# stm32hw03.net
KiCad netlist of a schematic drawn in EAGLE
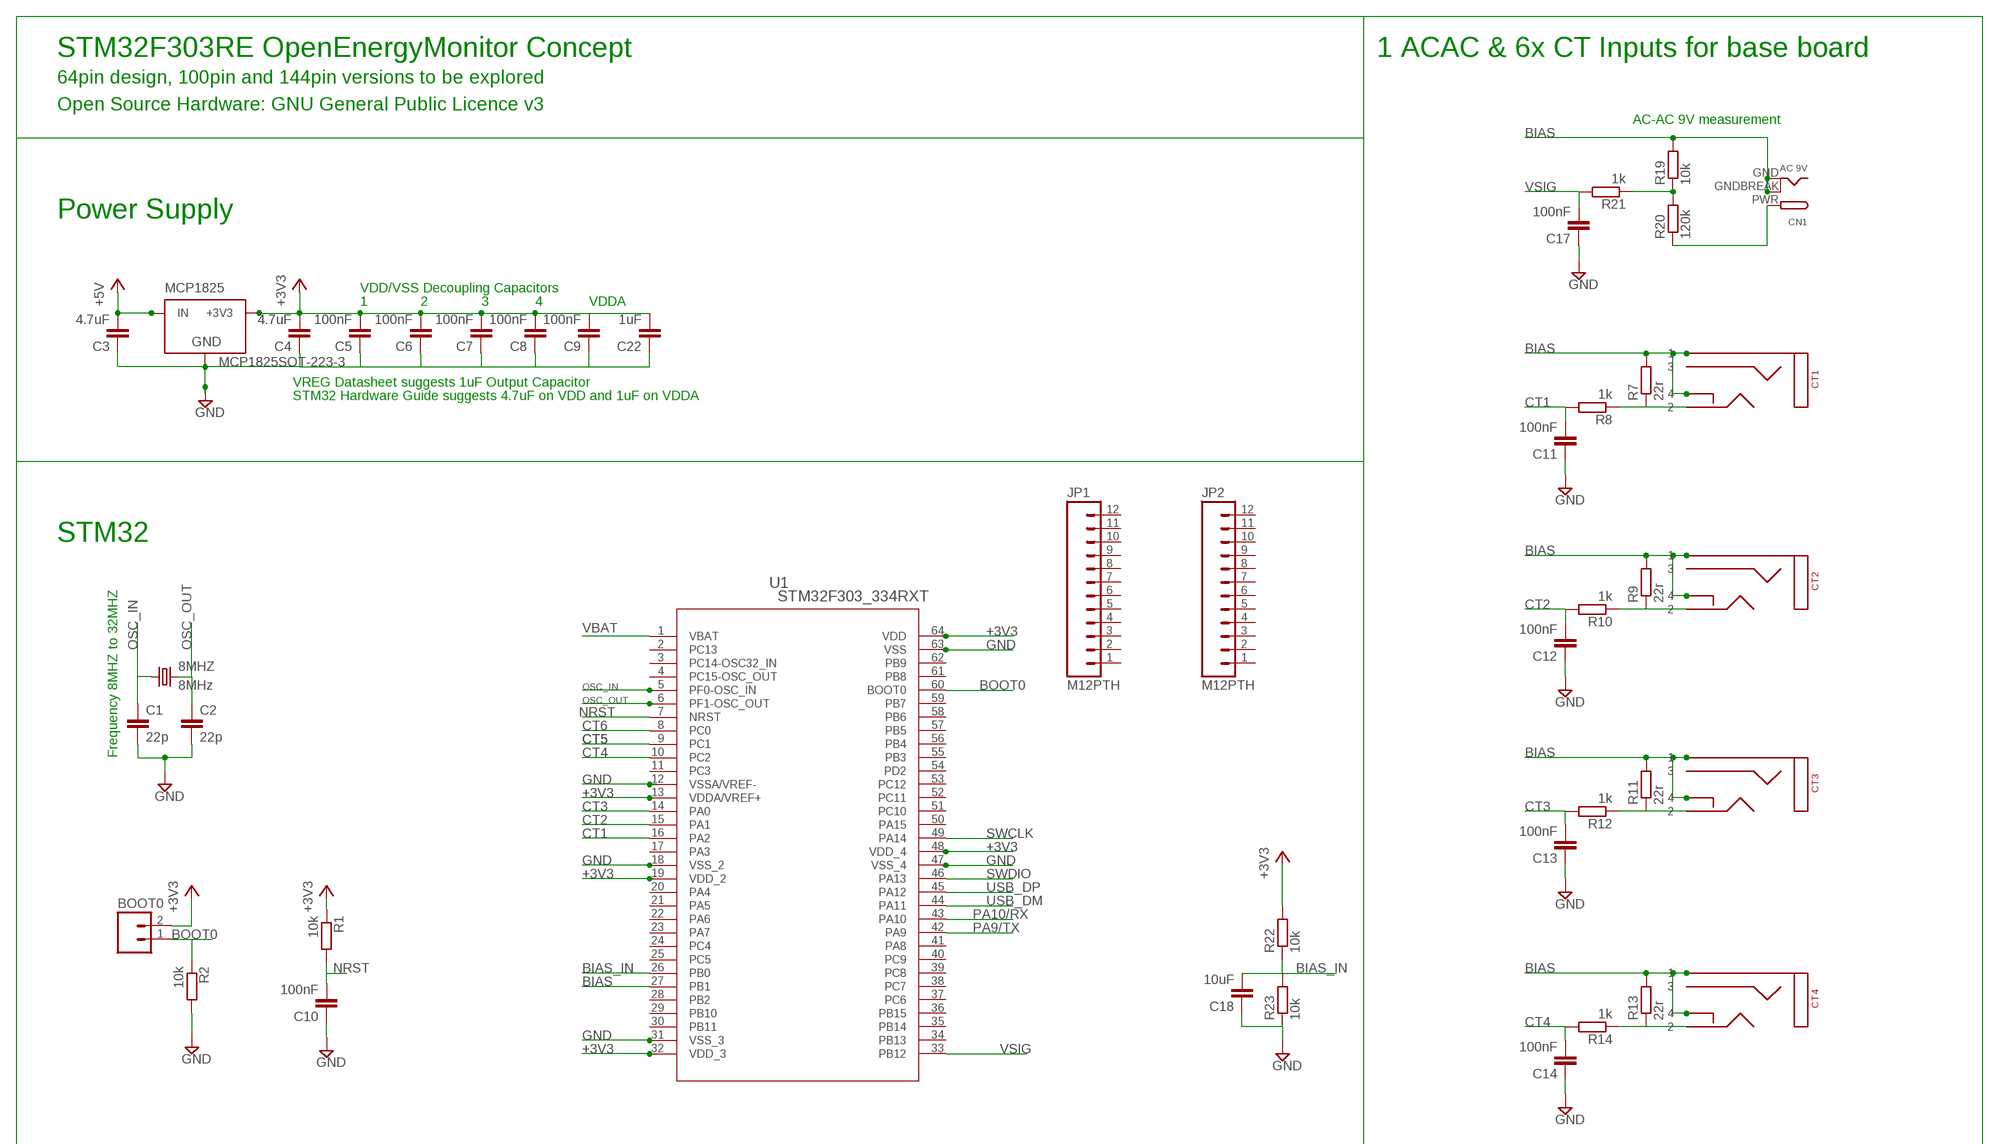
[diagram p0: schematic, sheet 1, part 1 of 2]
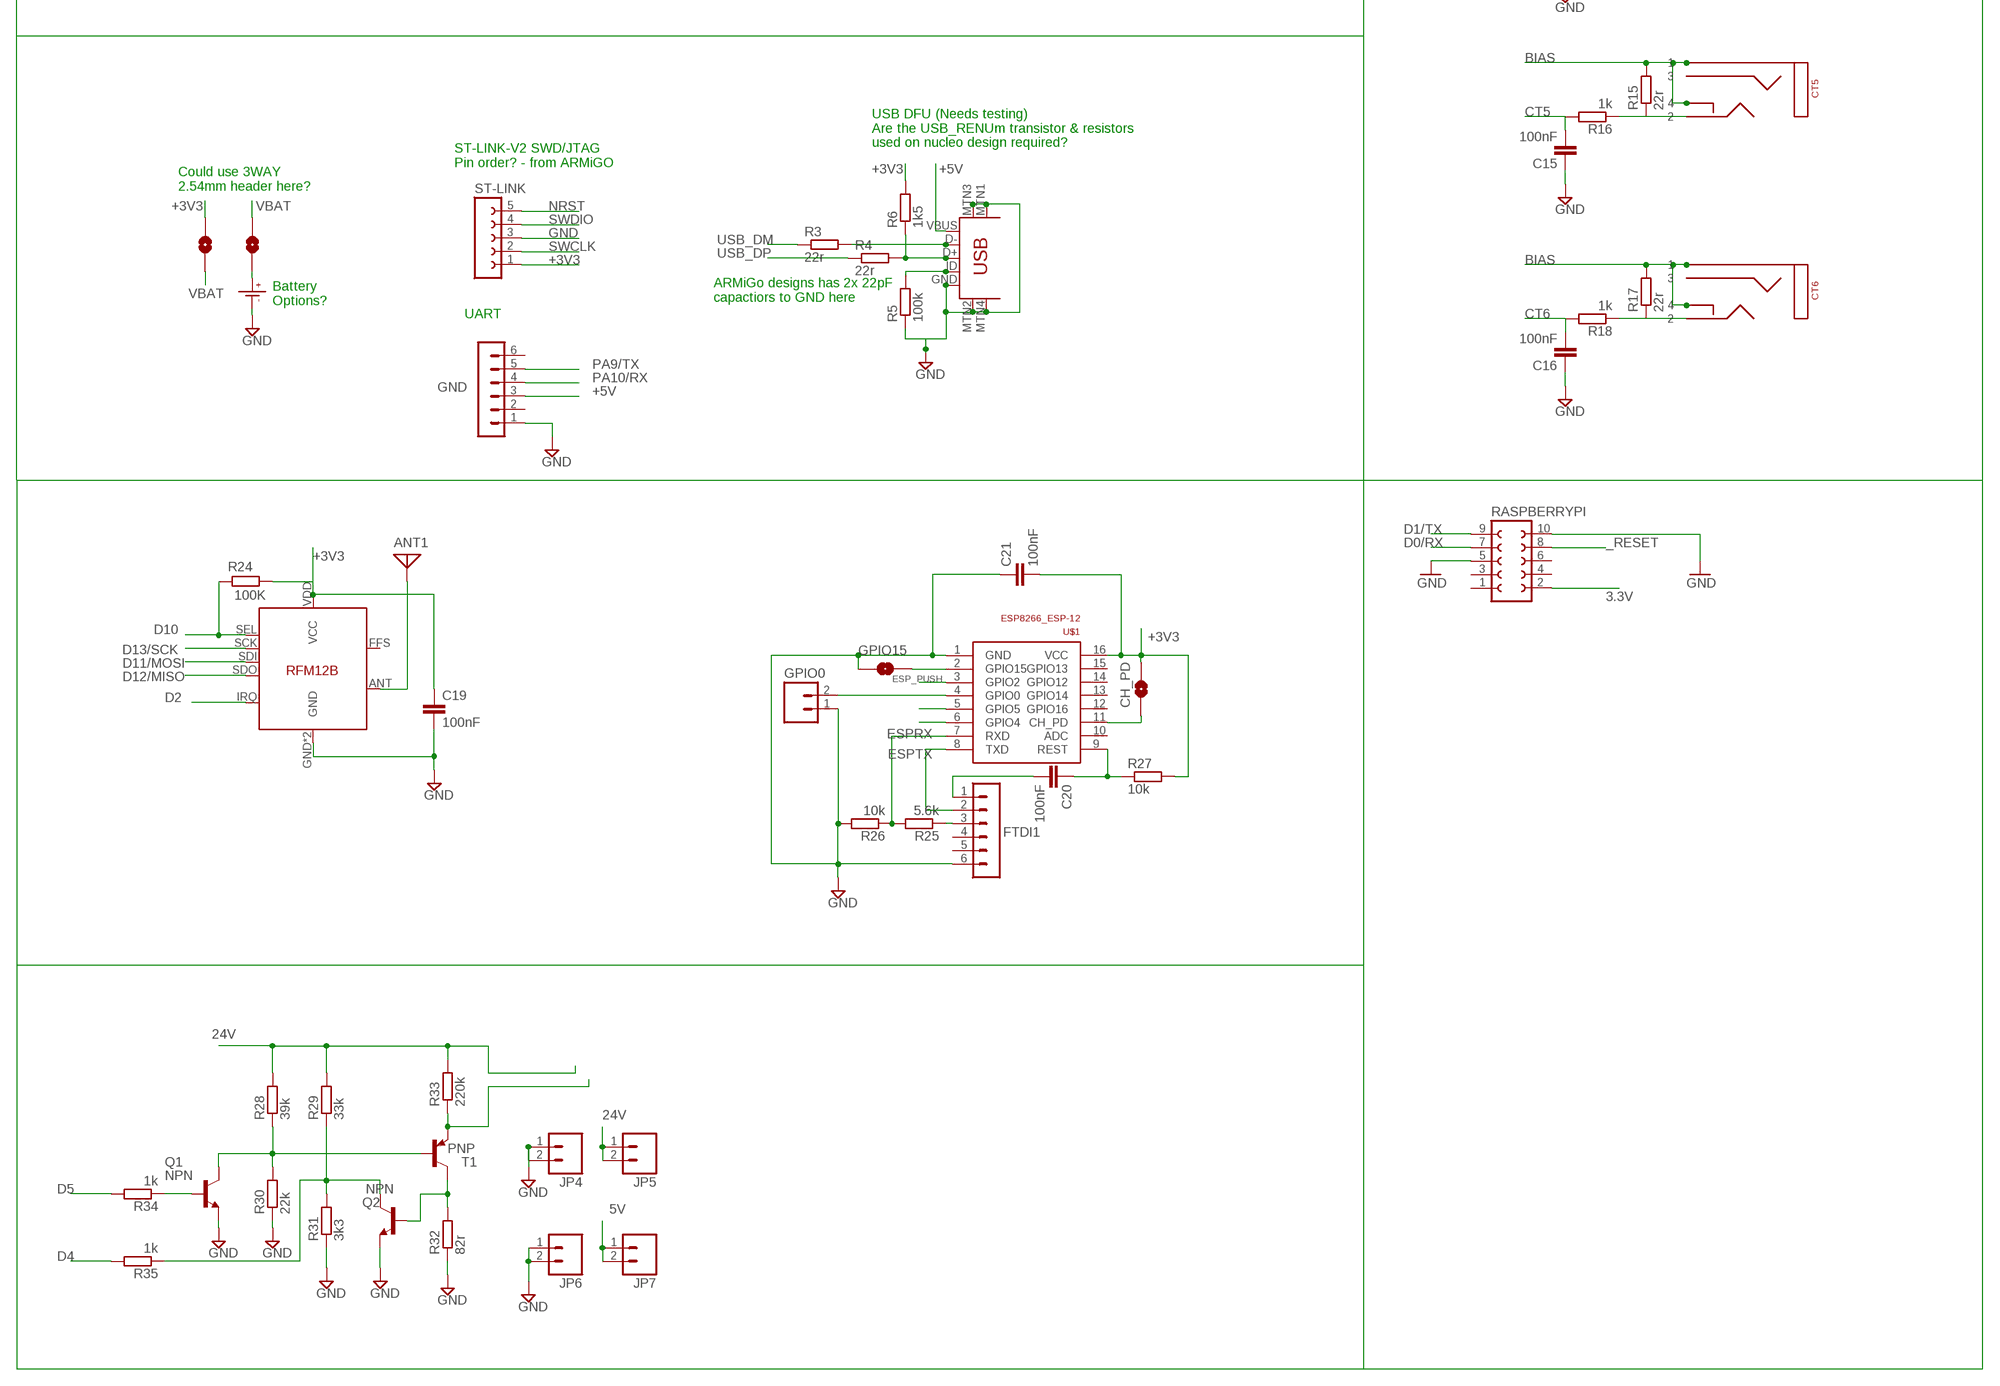
[diagram p1: schematic, sheet 1, part 2 of 2]

(export (version "E")
  (design (tool "Eeschema 10.0.6"))
  (components
    (comp (ref "3V3")
      (value "SOLDERJUMPERNO")
      (footprint "eagle-import:SJ_2S-NO")
      (libsource (lib "eagle-import") (part "SOLDERJUMPERNO"))
    )
    (comp (ref "8MHZ")
      (value "8MHz")
      (footprint "eagle-import:CRYSTAL-SMD-5X3")
      (libsource (lib "eagle-import") (part "CRYSTAL5X3"))
    )
    (comp (ref "ANT1")
      (value "ANTENNA")
      (footprint "eagle-import:PAD-01")
      (libsource (lib "eagle-import") (part "ANTENNA"))
    )
    (comp (ref "BATTERY")
      (value "SOLDERJUMPERNO")
      (footprint "eagle-import:SJ_2S-NO")
      (libsource (lib "eagle-import") (part "SOLDERJUMPERNO"))
    )
    (comp (ref "BOOT0")
      (value "M02PTH")
      (footprint "eagle-import:1X02")
      (libsource (lib "eagle-import") (part "M02PTH"))
    )
    (comp (ref "C1")
      (value "22p")
      (footprint "eagle-import:C0603")
      (libsource (lib "eagle-import") (part "C-EUC0603"))
    )
    (comp (ref "C2")
      (value "22p")
      (footprint "eagle-import:C0603")
      (libsource (lib "eagle-import") (part "C-EUC0603"))
    )
    (comp (ref "C3")
      (value "4.7uF")
      (footprint "eagle-import:C0603")
      (libsource (lib "eagle-import") (part "C-EUC0603"))
    )
    (comp (ref "C4")
      (value "4.7uF")
      (footprint "eagle-import:C0603")
      (libsource (lib "eagle-import") (part "C-EUC0603"))
    )
    (comp (ref "C5")
      (value "100nF")
      (footprint "eagle-import:C0603")
      (libsource (lib "eagle-import") (part "C-EUC0603"))
    )
    (comp (ref "C6")
      (value "100nF")
      (footprint "eagle-import:C0603")
      (libsource (lib "eagle-import") (part "C-EUC0603"))
    )
    (comp (ref "C7")
      (value "100nF")
      (footprint "eagle-import:C0603")
      (libsource (lib "eagle-import") (part "C-EUC0603"))
    )
    (comp (ref "C8")
      (value "100nF")
      (footprint "eagle-import:C0603")
      (libsource (lib "eagle-import") (part "C-EUC0603"))
    )
    (comp (ref "C9")
      (value "100nF")
      (footprint "eagle-import:C0603")
      (libsource (lib "eagle-import") (part "C-EUC0603"))
    )
    (comp (ref "C10")
      (value "100nF")
      (footprint "eagle-import:C0603")
      (libsource (lib "eagle-import") (part "C-EUC0603"))
    )
    (comp (ref "C11")
      (value "100nF")
      (footprint "eagle-import:C0603")
      (libsource (lib "eagle-import") (part "C-EUC0603"))
    )
    (comp (ref "C12")
      (value "100nF")
      (footprint "eagle-import:C0603")
      (libsource (lib "eagle-import") (part "C-EUC0603"))
    )
    (comp (ref "C13")
      (value "100nF")
      (footprint "eagle-import:C0603")
      (libsource (lib "eagle-import") (part "C-EUC0603"))
    )
    (comp (ref "C14")
      (value "100nF")
      (footprint "eagle-import:C0603")
      (libsource (lib "eagle-import") (part "C-EUC0603"))
    )
    (comp (ref "C15")
      (value "100nF")
      (footprint "eagle-import:C0603")
      (libsource (lib "eagle-import") (part "C-EUC0603"))
    )
    (comp (ref "C16")
      (value "100nF")
      (footprint "eagle-import:C0603")
      (libsource (lib "eagle-import") (part "C-EUC0603"))
    )
    (comp (ref "C17")
      (value "100nF")
      (footprint "eagle-import:C0603")
      (libsource (lib "eagle-import") (part "C-EUC0603"))
    )
    (comp (ref "C18")
      (value "10uF")
      (footprint "eagle-import:C0603")
      (libsource (lib "eagle-import") (part "C-EUC0603"))
    )
    (comp (ref "C19")
      (value "100nF")
      (footprint "eagle-import:C0603")
      (libsource (lib "eagle-import") (part "C-EUC0603"))
    )
    (comp (ref "C20")
      (value "100nF")
      (footprint "eagle-import:C0603")
      (libsource (lib "eagle-import") (part "C-EUC0603"))
    )
    (comp (ref "C21")
      (value "100nF")
      (footprint "eagle-import:C0603")
      (libsource (lib "eagle-import") (part "C-EUC0603"))
    )
    (comp (ref "C22")
      (value "1uF")
      (footprint "eagle-import:C0603")
      (libsource (lib "eagle-import") (part "C-EUC0603"))
    )
    (comp (ref "CH_PD")
      (value "SOLDERJUMPERNO")
      (footprint "eagle-import:SJ_2S-NO")
      (libsource (lib "eagle-import") (part "SOLDERJUMPERNO"))
    )
    (comp (ref "CN1")
      (value "AC 9V")
      (footprint "eagle-import:DCJACK_2MM_PTH")
      (libsource (lib "eagle-import") (part "DCBARRELPTH"))
    )
    (comp (ref "CR1220")
      (value "CR1220SMD")
      (footprint "eagle-import:CR1220SMD")
      (fields (field (name "MPN") "Harwin S8411-45R"))
      (libsource (lib "eagle-import") (part "CR1220SMD"))
    )
    (comp (ref "CT1")
      (value "STEREO_SMD")
      (footprint "eagle-import:STEREO_SMT")
      (libsource (lib "eagle-import") (part "STEREO_SMD"))
    )
    (comp (ref "CT2")
      (value "STEREO_SMD")
      (footprint "eagle-import:STEREO_SMT")
      (libsource (lib "eagle-import") (part "STEREO_SMD"))
    )
    (comp (ref "CT3")
      (value "STEREO_SMD")
      (footprint "eagle-import:STEREO_SMT")
      (libsource (lib "eagle-import") (part "STEREO_SMD"))
    )
    (comp (ref "CT4")
      (value "STEREO_SMD")
      (footprint "eagle-import:STEREO_SMT")
      (libsource (lib "eagle-import") (part "STEREO_SMD"))
    )
    (comp (ref "CT5")
      (value "STEREO_SMD")
      (footprint "eagle-import:STEREO_SMT")
      (libsource (lib "eagle-import") (part "STEREO_SMD"))
    )
    (comp (ref "CT6")
      (value "STEREO_SMD")
      (footprint "eagle-import:STEREO_SMT")
      (libsource (lib "eagle-import") (part "STEREO_SMD"))
    )
    (comp (ref "FTDI1")
      (value "FTDI")
      (footprint "eagle-import:MA06-1")
      (libsource (lib "eagle-import") (part "MA06-1"))
    )
    (comp (ref "GND")
      (value "UART")
      (footprint "eagle-import:MA06-1")
      (libsource (lib "eagle-import") (part "MA06-1"))
    )
    (comp (ref "GPIO0")
      (value "M02PTH")
      (footprint "eagle-import:1X02")
      (libsource (lib "eagle-import") (part "M02PTH"))
    )
    (comp (ref "GPIO15")
      (value "SOLDERJUMPERNO")
      (footprint "eagle-import:SJ_2S-NO")
      (libsource (lib "eagle-import") (part "SOLDERJUMPERNO"))
    )
    (comp (ref "JP1")
      (value "M12PTH")
      (footprint "eagle-import:1X12")
      (libsource (lib "eagle-import") (part "M12PTH"))
    )
    (comp (ref "JP2")
      (value "M12PTH")
      (footprint "eagle-import:1X12")
      (libsource (lib "eagle-import") (part "M12PTH"))
    )
    (comp (ref "JP4")
      (value "M02PTH")
      (footprint "eagle-import:1X02")
      (libsource (lib "eagle-import") (part "M02PTH"))
    )
    (comp (ref "JP5")
      (value "M02PTH")
      (footprint "eagle-import:1X02")
      (libsource (lib "eagle-import") (part "M02PTH"))
    )
    (comp (ref "JP6")
      (value "M02PTH")
      (footprint "eagle-import:1X02")
      (libsource (lib "eagle-import") (part "M02PTH"))
    )
    (comp (ref "JP7")
      (value "M02PTH")
      (footprint "eagle-import:1X02")
      (libsource (lib "eagle-import") (part "M02PTH"))
    )
    (comp (ref "MCP1825")
      (value "MCP1825SOT-223-3")
      (footprint "eagle-import:SOT-223")
      (libsource (lib "eagle-import") (part "MCP1825SOT-223-3"))
    )
    (comp (ref "Q1")
      (value "NPN")
      (footprint "eagle-import:SOT23-BEC")
      (libsource (lib "eagle-import") (part "BC849SMD"))
    )
    (comp (ref "Q2")
      (value "NPN")
      (footprint "eagle-import:SOT23-BEC")
      (libsource (lib "eagle-import") (part "BC849SMD"))
    )
    (comp (ref "R1")
      (value "10k")
      (footprint "eagle-import:R0603")
      (libsource (lib "eagle-import") (part "R-EU_R0603"))
    )
    (comp (ref "R2")
      (value "10k")
      (footprint "eagle-import:R0603")
      (libsource (lib "eagle-import") (part "R-EU_R0603"))
    )
    (comp (ref "R3")
      (value "22r")
      (footprint "eagle-import:R0603")
      (libsource (lib "eagle-import") (part "R-EU_R0603"))
    )
    (comp (ref "R4")
      (value "22r")
      (footprint "eagle-import:R0603")
      (libsource (lib "eagle-import") (part "R-EU_R0603"))
    )
    (comp (ref "R5")
      (value "100k")
      (footprint "eagle-import:R0603")
      (libsource (lib "eagle-import") (part "R-EU_R0603"))
    )
    (comp (ref "R6")
      (value "1k5")
      (footprint "eagle-import:R0603")
      (libsource (lib "eagle-import") (part "R-EU_R0603"))
    )
    (comp (ref "R7")
      (value "22r")
      (footprint "eagle-import:R0603")
      (libsource (lib "eagle-import") (part "R-EU_R0603"))
    )
    (comp (ref "R8")
      (value "1k")
      (footprint "eagle-import:R0603")
      (libsource (lib "eagle-import") (part "R-EU_R0603"))
    )
    (comp (ref "R9")
      (value "22r")
      (footprint "eagle-import:R0603")
      (libsource (lib "eagle-import") (part "R-EU_R0603"))
    )
    (comp (ref "R10")
      (value "1k")
      (footprint "eagle-import:R0603")
      (libsource (lib "eagle-import") (part "R-EU_R0603"))
    )
    (comp (ref "R11")
      (value "22r")
      (footprint "eagle-import:R0603")
      (libsource (lib "eagle-import") (part "R-EU_R0603"))
    )
    (comp (ref "R12")
      (value "1k")
      (footprint "eagle-import:R0603")
      (libsource (lib "eagle-import") (part "R-EU_R0603"))
    )
    (comp (ref "R13")
      (value "22r")
      (footprint "eagle-import:R0603")
      (libsource (lib "eagle-import") (part "R-EU_R0603"))
    )
    (comp (ref "R14")
      (value "1k")
      (footprint "eagle-import:R0603")
      (libsource (lib "eagle-import") (part "R-EU_R0603"))
    )
    (comp (ref "R15")
      (value "22r")
      (footprint "eagle-import:R0603")
      (libsource (lib "eagle-import") (part "R-EU_R0603"))
    )
    (comp (ref "R16")
      (value "1k")
      (footprint "eagle-import:R0603")
      (libsource (lib "eagle-import") (part "R-EU_R0603"))
    )
    (comp (ref "R17")
      (value "22r")
      (footprint "eagle-import:R0603")
      (libsource (lib "eagle-import") (part "R-EU_R0603"))
    )
    (comp (ref "R18")
      (value "1k")
      (footprint "eagle-import:R0603")
      (libsource (lib "eagle-import") (part "R-EU_R0603"))
    )
    (comp (ref "R19")
      (value "10k")
      (footprint "eagle-import:R0603")
      (libsource (lib "eagle-import") (part "R-EU_R0603"))
    )
    (comp (ref "R20")
      (value "120k")
      (footprint "eagle-import:R0603")
      (libsource (lib "eagle-import") (part "R-EU_R0603"))
    )
    (comp (ref "R21")
      (value "1k")
      (footprint "eagle-import:R0603")
      (libsource (lib "eagle-import") (part "R-EU_R0603"))
    )
    (comp (ref "R22")
      (value "10k")
      (footprint "eagle-import:R0603")
      (libsource (lib "eagle-import") (part "R-EU_R0603"))
    )
    (comp (ref "R23")
      (value "10k")
      (footprint "eagle-import:R0603")
      (libsource (lib "eagle-import") (part "R-EU_R0603"))
    )
    (comp (ref "R24")
      (value "100K")
      (footprint "eagle-import:R0603")
      (libsource (lib "eagle-import") (part "R-EU_R0603"))
    )
    (comp (ref "R25")
      (value "5.6k")
      (footprint "eagle-import:R0603")
      (libsource (lib "eagle-import") (part "R-EU_R0603"))
    )
    (comp (ref "R26")
      (value "10k")
      (footprint "eagle-import:R0603")
      (libsource (lib "eagle-import") (part "R-EU_R0603"))
    )
    (comp (ref "R27")
      (value "10k")
      (footprint "eagle-import:R0603")
      (libsource (lib "eagle-import") (part "R-EU_R0603"))
    )
    (comp (ref "R28")
      (value "39k")
      (footprint "eagle-import:R0603")
      (libsource (lib "eagle-import") (part "R-EU_R0603"))
    )
    (comp (ref "R29")
      (value "33k")
      (footprint "eagle-import:R0603")
      (libsource (lib "eagle-import") (part "R-EU_R0603"))
    )
    (comp (ref "R30")
      (value "22k")
      (footprint "eagle-import:R0603")
      (libsource (lib "eagle-import") (part "R-EU_R0603"))
    )
    (comp (ref "R31")
      (value "3k3")
      (footprint "eagle-import:R0603")
      (libsource (lib "eagle-import") (part "R-EU_R0603"))
    )
    (comp (ref "R32")
      (value "82r")
      (footprint "eagle-import:R0603")
      (libsource (lib "eagle-import") (part "R-EU_R0603"))
    )
    (comp (ref "R33")
      (value "220k")
      (footprint "eagle-import:R0603")
      (libsource (lib "eagle-import") (part "R-EU_R0603"))
    )
    (comp (ref "R34")
      (value "1k")
      (footprint "eagle-import:R0603")
      (libsource (lib "eagle-import") (part "R-EU_R0603"))
    )
    (comp (ref "R35")
      (value "1k")
      (footprint "eagle-import:R0603")
      (libsource (lib "eagle-import") (part "R-EU_R0603"))
    )
    (comp (ref "RASPBERRYPI")
      (value "FE05-2")
      (footprint "eagle-import:FE05-2")
      (libsource (lib "eagle-import") (part "FE05-2"))
    )
    (comp (ref "ST-LINK")
      (value "FE05-1")
      (footprint "eagle-import:FE05-1")
      (libsource (lib "eagle-import") (part "FE05-1"))
    )
    (comp (ref "T1")
      (value "PNP")
      (footprint "eagle-import:SOT23")
      (libsource (lib "eagle-import") (part "BCX71SMD"))
    )
    (comp (ref "U$1")
      (value "ESP8266_ESP-12")
      (footprint "eagle-import:ESP8266-ESP12")
      (libsource (lib "eagle-import") (part "ESP8266_ESP-12"))
    )
    (comp (ref "U$10")
      (value "USB-MINIB-5PIN")
      (footprint "eagle-import:USB-MINIB-CISECO")
      (libsource (lib "eagle-import") (part "USB-MINIB-5PIN"))
    )
    (comp (ref "U$14")
      (value "RFM12B")
      (footprint "eagle-import:RFM12B")
      (libsource (lib "eagle-import") (part "RFM12B"))
    )
    (comp (ref "U1")
      (value "STM32F303_334RXT")
      (footprint "eagle-import:LQFP64-10X10MM")
      (fields (field (name "MANUFACTURER_PART_NUMBER") "stm32f303_334rxt"))
      (libsource (lib "eagle-import") (part "STM32F303_334RXT"))
    )
  )
  (nets
    (net (code "1") (name "+3V3") (class "Default")
      (node (ref "3V3") (pin "1") (pinfunction "1_1") (pintype "passive"))
      (node (ref "BOOT0") (pin "2") (pinfunction "2_2") (pintype "passive"))
      (node (ref "C19") (pin "1") (pinfunction "1_1") (pintype "passive"))
      (node (ref "C21") (pin "2") (pinfunction "2_2") (pintype "passive"))
      (node (ref "C22") (pin "2") (pinfunction "2_2") (pintype "passive"))
      (node (ref "C4") (pin "2") (pinfunction "2_2") (pintype "passive"))
      (node (ref "C5") (pin "2") (pinfunction "2_2") (pintype "passive"))
      (node (ref "C6") (pin "2") (pinfunction "2_2") (pintype "passive"))
      (node (ref "C7") (pin "2") (pinfunction "2_2") (pintype "passive"))
      (node (ref "C8") (pin "2") (pinfunction "2_2") (pintype "passive"))
      (node (ref "C9") (pin "2") (pinfunction "2_2") (pintype "passive"))
      (node (ref "CH_PD") (pin "1") (pinfunction "1_1") (pintype "passive"))
      (node (ref "MCP1825") (pin "3") (pinfunction "+3V3_3") (pintype "power_in"))
      (node (ref "R1") (pin "1") (pinfunction "1_1") (pintype "passive"))
      (node (ref "R22") (pin "2") (pinfunction "2_2") (pintype "passive"))
      (node (ref "R24") (pin "1") (pinfunction "1_1") (pintype "passive"))
      (node (ref "R27") (pin "2") (pinfunction "2_2") (pintype "passive"))
      (node (ref "R6") (pin "2") (pinfunction "2_2") (pintype "passive"))
      (node (ref "ST-LINK") (pin "1") (pinfunction "1_1") (pintype "passive"))
      (node (ref "U$1") (pin "16") (pinfunction "VCC_16") (pintype "bidirectional"))
      (node (ref "U$14") (pin "VDD") (pinfunction "VCC_VDD") (pintype "power_in"))
      (node (ref "U1") (pin "13") (pinfunction "VDDA/VREF+_13") (pintype "power_in"))
      (node (ref "U1") (pin "19") (pinfunction "VDD_2_19") (pintype "power_in"))
      (node (ref "U1") (pin "32") (pinfunction "VDD_3_32") (pintype "power_in"))
      (node (ref "U1") (pin "48") (pinfunction "VDD_4_48") (pintype "power_in"))
      (node (ref "U1") (pin "64") (pinfunction "VDD_64") (pintype "power_in"))
    )
    (net (code "2") (name "+5V") (class "Default")
      (node (ref "C3") (pin "2") (pinfunction "2_2") (pintype "passive"))
      (node (ref "GND") (pin "3") (pinfunction "3_3") (pintype "passive"))
      (node (ref "MCP1825") (pin "1") (pinfunction "IN_1") (pintype "power_in"))
      (node (ref "U$10") (pin "VBUS") (pinfunction "VBUS_VBUS") (pintype "bidirectional"))
    )
    (net (code "3") (name "/3.3V") (class "Default")
      (node (ref "RASPBERRYPI") (pin "2") (pinfunction "2_2") (pintype "passive"))
    )
    (net (code "4") (name "/5V") (class "Default")
      (node (ref "JP7") (pin "1") (pinfunction "1_1") (pintype "passive"))
      (node (ref "JP7") (pin "2") (pinfunction "2_2") (pintype "passive"))
    )
    (net (code "5") (name "/24V") (class "Default")
      (node (ref "JP5") (pin "1") (pinfunction "1_1") (pintype "passive"))
      (node (ref "JP5") (pin "2") (pinfunction "2_2") (pintype "passive"))
      (node (ref "R28") (pin "2") (pinfunction "2_2") (pintype "passive"))
      (node (ref "R29") (pin "2") (pinfunction "2_2") (pintype "passive"))
      (node (ref "R33") (pin "2") (pinfunction "2_2") (pintype "passive"))
    )
    (net (code "6") (name "/BIAS") (class "Default")
      (node (ref "CN1") (pin "GND") (pinfunction "GND_GND") (pintype "power_in"))
      (node (ref "CN1") (pin "GNDBREAK") (pinfunction "GNDBREAK_GNDBREAK") (pintype "power_in"))
      (node (ref "CT1") (pin "P$1") (pinfunction "1_P$1") (pintype "bidirectional"))
      (node (ref "CT1") (pin "P$4") (pinfunction "4_P$4") (pintype "bidirectional"))
      (node (ref "CT2") (pin "P$1") (pinfunction "1_P$1") (pintype "bidirectional"))
      (node (ref "CT2") (pin "P$4") (pinfunction "4_P$4") (pintype "bidirectional"))
      (node (ref "CT3") (pin "P$1") (pinfunction "1_P$1") (pintype "bidirectional"))
      (node (ref "CT3") (pin "P$4") (pinfunction "4_P$4") (pintype "bidirectional"))
      (node (ref "CT4") (pin "P$1") (pinfunction "1_P$1") (pintype "bidirectional"))
      (node (ref "CT4") (pin "P$4") (pinfunction "4_P$4") (pintype "bidirectional"))
      (node (ref "CT5") (pin "P$1") (pinfunction "1_P$1") (pintype "bidirectional"))
      (node (ref "CT5") (pin "P$4") (pinfunction "4_P$4") (pintype "bidirectional"))
      (node (ref "CT6") (pin "P$1") (pinfunction "1_P$1") (pintype "bidirectional"))
      (node (ref "CT6") (pin "P$4") (pinfunction "4_P$4") (pintype "bidirectional"))
      (node (ref "R11") (pin "2") (pinfunction "2_2") (pintype "passive"))
      (node (ref "R13") (pin "2") (pinfunction "2_2") (pintype "passive"))
      (node (ref "R15") (pin "2") (pinfunction "2_2") (pintype "passive"))
      (node (ref "R17") (pin "2") (pinfunction "2_2") (pintype "passive"))
      (node (ref "R19") (pin "2") (pinfunction "2_2") (pintype "passive"))
      (node (ref "R7") (pin "2") (pinfunction "2_2") (pintype "passive"))
      (node (ref "R9") (pin "2") (pinfunction "2_2") (pintype "passive"))
      (node (ref "U1") (pin "27") (pinfunction "PB1_27") (pintype "bidirectional"))
    )
    (net (code "7") (name "/BIAS_IN") (class "Default")
      (node (ref "C18") (pin "2") (pinfunction "2_2") (pintype "passive"))
      (node (ref "R22") (pin "1") (pinfunction "1_1") (pintype "passive"))
      (node (ref "R23") (pin "2") (pinfunction "2_2") (pintype "passive"))
      (node (ref "U1") (pin "26") (pinfunction "PB0_26") (pintype "bidirectional"))
    )
    (net (code "8") (name "/BOOT0") (class "Default")
      (node (ref "BOOT0") (pin "1") (pinfunction "1_1") (pintype "passive"))
      (node (ref "R2") (pin "1") (pinfunction "1_1") (pintype "passive"))
      (node (ref "U1") (pin "60") (pinfunction "BOOT0_60") (pintype "input"))
    )
    (net (code "9") (name "/CT1") (class "Default")
      (node (ref "C11") (pin "2") (pinfunction "2_2") (pintype "passive"))
      (node (ref "R8") (pin "2") (pinfunction "2_2") (pintype "passive"))
      (node (ref "U1") (pin "16") (pinfunction "PA2_16") (pintype "bidirectional"))
    )
    (net (code "10") (name "/CT2") (class "Default")
      (node (ref "C12") (pin "2") (pinfunction "2_2") (pintype "passive"))
      (node (ref "R10") (pin "2") (pinfunction "2_2") (pintype "passive"))
      (node (ref "U1") (pin "15") (pinfunction "PA1_15") (pintype "bidirectional"))
    )
    (net (code "11") (name "/CT3") (class "Default")
      (node (ref "C13") (pin "2") (pinfunction "2_2") (pintype "passive"))
      (node (ref "R12") (pin "2") (pinfunction "2_2") (pintype "passive"))
      (node (ref "U1") (pin "14") (pinfunction "PA0_14") (pintype "bidirectional"))
    )
    (net (code "12") (name "/CT4") (class "Default")
      (node (ref "C14") (pin "2") (pinfunction "2_2") (pintype "passive"))
      (node (ref "R14") (pin "2") (pinfunction "2_2") (pintype "passive"))
      (node (ref "U1") (pin "10") (pinfunction "PC2_10") (pintype "bidirectional"))
    )
    (net (code "13") (name "/CT5") (class "Default")
      (node (ref "C15") (pin "2") (pinfunction "2_2") (pintype "passive"))
      (node (ref "R16") (pin "2") (pinfunction "2_2") (pintype "passive"))
      (node (ref "U1") (pin "9") (pinfunction "PC1_9") (pintype "bidirectional"))
    )
    (net (code "14") (name "/CT6") (class "Default")
      (node (ref "C16") (pin "2") (pinfunction "2_2") (pintype "passive"))
      (node (ref "R18") (pin "2") (pinfunction "2_2") (pintype "passive"))
      (node (ref "U1") (pin "8") (pinfunction "PC0_8") (pintype "bidirectional"))
    )
    (net (code "15") (name "/D0{slash}RX") (class "Default")
      (node (ref "RASPBERRYPI") (pin "7") (pinfunction "7_7") (pintype "passive"))
    )
    (net (code "16") (name "/D1{slash}TX") (class "Default")
      (node (ref "RASPBERRYPI") (pin "9") (pinfunction "9_9") (pintype "passive"))
    )
    (net (code "17") (name "/D2") (class "Default")
      (node (ref "U$14") (pin "IRQ") (pinfunction "IRQ_IRQ") (pintype "open_collector"))
    )
    (net (code "18") (name "/D4") (class "Default")
      (node (ref "R35") (pin "2") (pinfunction "2_2") (pintype "passive"))
    )
    (net (code "19") (name "/D5") (class "Default")
      (node (ref "R34") (pin "2") (pinfunction "2_2") (pintype "passive"))
    )
    (net (code "20") (name "/D10") (class "Default")
      (node (ref "R24") (pin "2") (pinfunction "2_2") (pintype "passive"))
      (node (ref "U$14") (pin "SEL") (pinfunction "SEL_SEL") (pintype "input"))
    )
    (net (code "21") (name "/D11{slash}MOSI") (class "Default")
      (node (ref "U$14") (pin "SDI") (pinfunction "SDI_SDI") (pintype "input"))
    )
    (net (code "22") (name "/D12{slash}MISO") (class "Default")
      (node (ref "U$14") (pin "SDO") (pinfunction "SDO_SDO") (pintype "output"))
    )
    (net (code "23") (name "/D13{slash}SCK") (class "Default")
      (node (ref "U$14") (pin "SCK") (pinfunction "SCK_SCK") (pintype "input"))
    )
    (net (code "24") (name "/ESPRX") (class "Default")
      (node (ref "R25") (pin "2") (pinfunction "2_2") (pintype "passive"))
      (node (ref "R26") (pin "1") (pinfunction "1_1") (pintype "passive"))
      (node (ref "U$1") (pin "7") (pinfunction "RXD_7") (pintype "bidirectional"))
    )
    (net (code "25") (name "/ESPTX") (class "Default")
      (node (ref "FTDI1") (pin "2") (pinfunction "2_2") (pintype "passive"))
      (node (ref "U$1") (pin "8") (pinfunction "TXD_8") (pintype "bidirectional"))
    )
    (net (code "26") (name "/ESP_PUSH") (class "Default")
      (node (ref "U$1") (pin "3") (pinfunction "GPIO2_3") (pintype "bidirectional"))
    )
    (net (code "27") (name "/NRST") (class "Default")
      (node (ref "C10") (pin "2") (pinfunction "2_2") (pintype "passive"))
      (node (ref "R1") (pin "2") (pinfunction "2_2") (pintype "passive"))
      (node (ref "ST-LINK") (pin "5") (pinfunction "5_5") (pintype "passive"))
      (node (ref "U1") (pin "7") (pinfunction "NRST_7") (pintype "bidirectional"))
    )
    (net (code "28") (name "/OSC_IN") (class "Default")
      (node (ref "8MHZ") (pin "1") (pinfunction "1_1") (pintype "passive"))
      (node (ref "C1") (pin "1") (pinfunction "1_1") (pintype "passive"))
      (node (ref "U1") (pin "5") (pinfunction "PF0-OSC_IN_5") (pintype "bidirectional"))
    )
    (net (code "29") (name "/OSC_OUT") (class "Default")
      (node (ref "8MHZ") (pin "3") (pinfunction "2_3") (pintype "passive"))
      (node (ref "C2") (pin "1") (pinfunction "1_1") (pintype "passive"))
      (node (ref "U1") (pin "6") (pinfunction "PF1-OSC_OUT_6") (pintype "bidirectional"))
    )
    (net (code "30") (name "/PA9{slash}TX") (class "Default")
      (node (ref "GND") (pin "5") (pinfunction "5_5") (pintype "passive"))
      (node (ref "U1") (pin "42") (pinfunction "PA9_42") (pintype "bidirectional"))
    )
    (net (code "31") (name "/PA10{slash}RX") (class "Default")
      (node (ref "GND") (pin "4") (pinfunction "4_4") (pintype "passive"))
      (node (ref "U1") (pin "43") (pinfunction "PA10_43") (pintype "bidirectional"))
    )
    (net (code "32") (name "/SWCLK") (class "Default")
      (node (ref "ST-LINK") (pin "2") (pinfunction "2_2") (pintype "passive"))
      (node (ref "U1") (pin "49") (pinfunction "PA14_49") (pintype "bidirectional"))
    )
    (net (code "33") (name "/SWDIO") (class "Default")
      (node (ref "ST-LINK") (pin "4") (pinfunction "4_4") (pintype "passive"))
      (node (ref "U1") (pin "46") (pinfunction "PA13_46") (pintype "bidirectional"))
    )
    (net (code "34") (name "/USB_DM") (class "Default")
      (node (ref "R3") (pin "1") (pinfunction "1_1") (pintype "passive"))
      (node (ref "U1") (pin "44") (pinfunction "PA11_44") (pintype "bidirectional"))
    )
    (net (code "35") (name "/USB_DP") (class "Default")
      (node (ref "R4") (pin "1") (pinfunction "1_1") (pintype "passive"))
      (node (ref "U1") (pin "45") (pinfunction "PA12_45") (pintype "bidirectional"))
    )
    (net (code "36") (name "/VBAT") (class "Default")
      (node (ref "3V3") (pin "2") (pinfunction "2_2") (pintype "passive"))
      (node (ref "BATTERY") (pin "1") (pinfunction "1_1") (pintype "passive"))
      (node (ref "U1") (pin "1") (pinfunction "VBAT_1") (pintype "power_in"))
    )
    (net (code "37") (name "/VSIG") (class "Default")
      (node (ref "C17") (pin "2") (pinfunction "2_2") (pintype "passive"))
      (node (ref "R21") (pin "2") (pinfunction "2_2") (pintype "passive"))
      (node (ref "U1") (pin "33") (pinfunction "PB12_33") (pintype "bidirectional"))
    )
    (net (code "38") (name "/_RESET") (class "Default")
      (node (ref "RASPBERRYPI") (pin "8") (pinfunction "8_8") (pintype "passive"))
    )
    (net (code "39") (name "GND") (class "Default")
      (node (ref "C1") (pin "2") (pinfunction "2_2") (pintype "passive"))
      (node (ref "C10") (pin "1") (pinfunction "1_1") (pintype "passive"))
      (node (ref "C11") (pin "1") (pinfunction "1_1") (pintype "passive"))
      (node (ref "C12") (pin "1") (pinfunction "1_1") (pintype "passive"))
      (node (ref "C13") (pin "1") (pinfunction "1_1") (pintype "passive"))
      (node (ref "C14") (pin "1") (pinfunction "1_1") (pintype "passive"))
      (node (ref "C15") (pin "1") (pinfunction "1_1") (pintype "passive"))
      (node (ref "C16") (pin "1") (pinfunction "1_1") (pintype "passive"))
      (node (ref "C17") (pin "1") (pinfunction "1_1") (pintype "passive"))
      (node (ref "C18") (pin "1") (pinfunction "1_1") (pintype "passive"))
      (node (ref "C19") (pin "2") (pinfunction "2_2") (pintype "passive"))
      (node (ref "C2") (pin "2") (pinfunction "2_2") (pintype "passive"))
      (node (ref "C21") (pin "1") (pinfunction "1_1") (pintype "passive"))
      (node (ref "C22") (pin "1") (pinfunction "1_1") (pintype "passive"))
      (node (ref "C3") (pin "1") (pinfunction "1_1") (pintype "passive"))
      (node (ref "C4") (pin "1") (pinfunction "1_1") (pintype "passive"))
      (node (ref "C5") (pin "1") (pinfunction "1_1") (pintype "passive"))
      (node (ref "C6") (pin "1") (pinfunction "1_1") (pintype "passive"))
      (node (ref "C7") (pin "1") (pinfunction "1_1") (pintype "passive"))
      (node (ref "C8") (pin "1") (pinfunction "1_1") (pintype "passive"))
      (node (ref "C9") (pin "1") (pinfunction "1_1") (pintype "passive"))
      (node (ref "CR1220") (pin "P-") (pinfunction "P$-_P-") (pintype "bidirectional"))
      (node (ref "FTDI1") (pin "6") (pinfunction "6_6") (pintype "passive"))
      (node (ref "GND") (pin "1") (pinfunction "1_1") (pintype "passive"))
      (node (ref "GPIO0") (pin "1") (pinfunction "1_1") (pintype "passive"))
      (node (ref "GPIO15") (pin "2") (pinfunction "2_2") (pintype "passive"))
      (node (ref "JP4") (pin "1") (pinfunction "1_1") (pintype "passive"))
      (node (ref "JP4") (pin "2") (pinfunction "2_2") (pintype "passive"))
      (node (ref "JP6") (pin "1") (pinfunction "1_1") (pintype "passive"))
      (node (ref "JP6") (pin "2") (pinfunction "2_2") (pintype "passive"))
      (node (ref "MCP1825") (pin "2") (pinfunction "GND_2") (pintype "power_in"))
      (node (ref "Q1") (pin "E") (pinfunction "E_E") (pintype "passive"))
      (node (ref "Q2") (pin "E") (pinfunction "E_E") (pintype "passive"))
      (node (ref "R2") (pin "2") (pinfunction "2_2") (pintype "passive"))
      (node (ref "R23") (pin "1") (pinfunction "1_1") (pintype "passive"))
      (node (ref "R26") (pin "2") (pinfunction "2_2") (pintype "passive"))
      (node (ref "R30") (pin "1") (pinfunction "1_1") (pintype "passive"))
      (node (ref "R31") (pin "1") (pinfunction "1_1") (pintype "passive"))
      (node (ref "R32") (pin "1") (pinfunction "1_1") (pintype "passive"))
      (node (ref "R5") (pin "1") (pinfunction "1_1") (pintype "passive"))
      (node (ref "RASPBERRYPI") (pin "10") (pinfunction "10_10") (pintype "passive"))
      (node (ref "RASPBERRYPI") (pin "5") (pinfunction "5_5") (pintype "passive"))
      (node (ref "ST-LINK") (pin "3") (pinfunction "3_3") (pintype "passive"))
      (node (ref "U$1") (pin "1") (pinfunction "GND_1") (pintype "bidirectional"))
      (node (ref "U$10") (pin "GND") (pinfunction "GND_GND") (pintype "bidirectional"))
      (node (ref "U$10") (pin "MTN1") (pinfunction "MTN2_MTN1") (pintype "bidirectional"))
      (node (ref "U$10") (pin "MTN2") (pinfunction "MTN3_MTN2") (pintype "bidirectional"))
      (node (ref "U$10") (pin "MTN3") (pinfunction "MTN1_MTN3") (pintype "bidirectional"))
      (node (ref "U$10") (pin "MTN4") (pinfunction "MTN4_MTN4") (pintype "bidirectional"))
      (node (ref "U$14") (pin "GND") (pinfunction "GND_GND") (pintype "power_in"))
      (node (ref "U$14") (pin "P$12") (pinfunction "GND_P$12") (pintype "power_in"))
      (node (ref "U1") (pin "12") (pinfunction "VSSA/VREF-_12") (pintype "power_in"))
      (node (ref "U1") (pin "18") (pinfunction "VSS_2_18") (pintype "power_in"))
      (node (ref "U1") (pin "31") (pinfunction "VSS_3_31") (pintype "power_in"))
      (node (ref "U1") (pin "47") (pinfunction "VSS_4_47") (pintype "power_in"))
      (node (ref "U1") (pin "63") (pinfunction "VSS_63") (pintype "power_in"))
    )
    (net (code "40") (name "Net-(ANT1-Pad1)") (class "Default")
      (node (ref "ANT1") (pin "1") (pinfunction "1_1") (pintype "output"))
      (node (ref "U$14") (pin "ANT") (pinfunction "ANT_ANT") (pintype "passive"))
    )
    (net (code "41") (name "Net-(C20-Pad2)") (class "Default")
      (node (ref "C20") (pin "2") (pinfunction "2_2") (pintype "passive"))
      (node (ref "FTDI1") (pin "1") (pinfunction "1_1") (pintype "passive"))
    )
    (net (code "42") (name "Net-(CN1-PadPWR)") (class "Default")
      (node (ref "CN1") (pin "PWR") (pinfunction "PWR_PWR") (pintype "power_in"))
      (node (ref "R20") (pin "1") (pinfunction "1_1") (pintype "passive"))
    )
    (net (code "43") (name "Net-(CR1220-P$+)") (class "Default")
      (node (ref "BATTERY") (pin "2") (pinfunction "2_2") (pintype "passive"))
      (node (ref "CR1220") (pin "P+") (pinfunction "P$+_P+") (pintype "bidirectional"))
    )
    (net (code "44") (name "Net-(CT1-2)") (class "Default")
      (node (ref "CT1") (pin "P$2") (pinfunction "2_P$2") (pintype "bidirectional"))
      (node (ref "R7") (pin "1") (pinfunction "1_1") (pintype "passive"))
      (node (ref "R8") (pin "1") (pinfunction "1_1") (pintype "passive"))
    )
    (net (code "45") (name "Net-(CT2-2)") (class "Default")
      (node (ref "CT2") (pin "P$2") (pinfunction "2_P$2") (pintype "bidirectional"))
      (node (ref "R10") (pin "1") (pinfunction "1_1") (pintype "passive"))
      (node (ref "R9") (pin "1") (pinfunction "1_1") (pintype "passive"))
    )
    (net (code "46") (name "Net-(CT3-2)") (class "Default")
      (node (ref "CT3") (pin "P$2") (pinfunction "2_P$2") (pintype "bidirectional"))
      (node (ref "R11") (pin "1") (pinfunction "1_1") (pintype "passive"))
      (node (ref "R12") (pin "1") (pinfunction "1_1") (pintype "passive"))
    )
    (net (code "47") (name "Net-(CT4-2)") (class "Default")
      (node (ref "CT4") (pin "P$2") (pinfunction "2_P$2") (pintype "bidirectional"))
      (node (ref "R13") (pin "1") (pinfunction "1_1") (pintype "passive"))
      (node (ref "R14") (pin "1") (pinfunction "1_1") (pintype "passive"))
    )
    (net (code "48") (name "Net-(CT5-2)") (class "Default")
      (node (ref "CT5") (pin "P$2") (pinfunction "2_P$2") (pintype "bidirectional"))
      (node (ref "R15") (pin "1") (pinfunction "1_1") (pintype "passive"))
      (node (ref "R16") (pin "1") (pinfunction "1_1") (pintype "passive"))
    )
    (net (code "49") (name "Net-(CT6-2)") (class "Default")
      (node (ref "CT6") (pin "P$2") (pinfunction "2_P$2") (pintype "bidirectional"))
      (node (ref "R17") (pin "1") (pinfunction "1_1") (pintype "passive"))
      (node (ref "R18") (pin "1") (pinfunction "1_1") (pintype "passive"))
    )
    (net (code "50") (name "Net-(FTDI1-Pad3)") (class "Default")
      (node (ref "FTDI1") (pin "3") (pinfunction "3_3") (pintype "passive"))
      (node (ref "R25") (pin "1") (pinfunction "1_1") (pintype "passive"))
    )
    (net (code "51") (name "Net-(Q1-PadB)") (class "Default")
      (node (ref "Q1") (pin "B") (pinfunction "B_B") (pintype "passive"))
      (node (ref "R34") (pin "1") (pinfunction "1_1") (pintype "passive"))
    )
    (net (code "52") (name "Net-(Q2-PadC)") (class "Default")
      (node (ref "Q2") (pin "C") (pinfunction "C_C") (pintype "passive"))
      (node (ref "R29") (pin "1") (pinfunction "1_1") (pintype "passive"))
      (node (ref "R31") (pin "2") (pinfunction "2_2") (pintype "passive"))
      (node (ref "R35") (pin "1") (pinfunction "1_1") (pintype "passive"))
    )
    (net (code "53") (name "Net-(R3-Pad2)") (class "Default")
      (node (ref "R3") (pin "2") (pinfunction "2_2") (pintype "passive"))
      (node (ref "U$10") (pin "D-") (pinfunction "D-_D-") (pintype "bidirectional"))
    )
    (net (code "54") (name "Net-(R4-Pad2)") (class "Default")
      (node (ref "R4") (pin "2") (pinfunction "2_2") (pintype "passive"))
      (node (ref "R6") (pin "1") (pinfunction "1_1") (pintype "passive"))
      (node (ref "U$10") (pin "D+") (pinfunction "D+_D+") (pintype "bidirectional"))
    )
    (net (code "55") (name "Net-(R5-Pad2)") (class "Default")
      (node (ref "R5") (pin "2") (pinfunction "2_2") (pintype "passive"))
      (node (ref "U$10") (pin "ID") (pinfunction "ID_ID") (pintype "bidirectional"))
    )
    (net (code "56") (name "Net-(R19-Pad1)") (class "Default")
      (node (ref "R19") (pin "1") (pinfunction "1_1") (pintype "passive"))
      (node (ref "R20") (pin "2") (pinfunction "2_2") (pintype "passive"))
      (node (ref "R21") (pin "1") (pinfunction "1_1") (pintype "passive"))
    )
    (net (code "57") (name "Net-(T1-B)") (class "Default")
      (node (ref "Q1") (pin "C") (pinfunction "C_C") (pintype "passive"))
      (node (ref "R28") (pin "1") (pinfunction "1_1") (pintype "passive"))
      (node (ref "R30") (pin "2") (pinfunction "2_2") (pintype "passive"))
      (node (ref "T1") (pin "1") (pinfunction "B_1") (pintype "passive"))
    )
    (net (code "58") (name "Net-(T1-C)") (class "Default")
      (node (ref "Q2") (pin "B") (pinfunction "B_B") (pintype "passive"))
      (node (ref "R32") (pin "2") (pinfunction "2_2") (pintype "passive"))
      (node (ref "T1") (pin "3") (pinfunction "C_3") (pintype "passive"))
    )
    (net (code "59") (name "Net-(T1-E)") (class "Default")
      (node (ref "R33") (pin "1") (pinfunction "1_1") (pintype "passive"))
      (node (ref "T1") (pin "2") (pinfunction "E_2") (pintype "passive"))
    )
    (net (code "60") (name "Net-(U$1-CH_PD)") (class "Default")
      (node (ref "CH_PD") (pin "2") (pinfunction "2_2") (pintype "passive"))
      (node (ref "U$1") (pin "11") (pinfunction "CH_PD_11") (pintype "bidirectional"))
    )
    (net (code "61") (name "Net-(U$1-GPIO0)") (class "Default")
      (node (ref "GPIO0") (pin "2") (pinfunction "2_2") (pintype "passive"))
      (node (ref "U$1") (pin "4") (pinfunction "GPIO0_4") (pintype "bidirectional"))
    )
    (net (code "62") (name "Net-(U$1-GPIO15)") (class "Default")
      (node (ref "GPIO15") (pin "1") (pinfunction "1_1") (pintype "passive"))
      (node (ref "U$1") (pin "2") (pinfunction "GPIO15_2") (pintype "bidirectional"))
    )
    (net (code "63") (name "Net-(U$1-REST)") (class "Default")
      (node (ref "C20") (pin "1") (pinfunction "1_1") (pintype "passive"))
      (node (ref "R27") (pin "1") (pinfunction "1_1") (pintype "passive"))
      (node (ref "U$1") (pin "9") (pinfunction "REST_9") (pintype "bidirectional"))
    )
    (net (code "64") (name "unconnected-(CT1-3-PadP$3)") (class "Default")
      (node (ref "CT1") (pin "P$3") (pinfunction "3_P$3") (pintype "bidirectional"))
    )
    (net (code "65") (name "unconnected-(CT2-3-PadP$3)") (class "Default")
      (node (ref "CT2") (pin "P$3") (pinfunction "3_P$3") (pintype "bidirectional"))
    )
    (net (code "66") (name "unconnected-(CT3-3-PadP$3)") (class "Default")
      (node (ref "CT3") (pin "P$3") (pinfunction "3_P$3") (pintype "bidirectional"))
    )
    (net (code "67") (name "unconnected-(CT4-3-PadP$3)") (class "Default")
      (node (ref "CT4") (pin "P$3") (pinfunction "3_P$3") (pintype "bidirectional"))
    )
    (net (code "68") (name "unconnected-(CT5-3-PadP$3)") (class "Default")
      (node (ref "CT5") (pin "P$3") (pinfunction "3_P$3") (pintype "bidirectional"))
    )
    (net (code "69") (name "unconnected-(CT6-3-PadP$3)") (class "Default")
      (node (ref "CT6") (pin "P$3") (pinfunction "3_P$3") (pintype "bidirectional"))
    )
    (net (code "70") (name "unconnected-(FTDI1-Pad4)") (class "Default")
      (node (ref "FTDI1") (pin "4") (pinfunction "4_4") (pintype "passive"))
    )
    (net (code "71") (name "unconnected-(FTDI1-Pad5)") (class "Default")
      (node (ref "FTDI1") (pin "5") (pinfunction "5_5") (pintype "passive"))
    )
    (net (code "72") (name "unconnected-(GND-Pad2)") (class "Default")
      (node (ref "GND") (pin "2") (pinfunction "2_2") (pintype "passive"))
    )
    (net (code "73") (name "unconnected-(GND-Pad6)") (class "Default")
      (node (ref "GND") (pin "6") (pinfunction "6_6") (pintype "passive"))
    )
    (net (code "74") (name "unconnected-(JP1-Pad1)") (class "Default")
      (node (ref "JP1") (pin "1") (pinfunction "1_1") (pintype "passive"))
    )
    (net (code "75") (name "unconnected-(JP1-Pad2)") (class "Default")
      (node (ref "JP1") (pin "2") (pinfunction "2_2") (pintype "passive"))
    )
    (net (code "76") (name "unconnected-(JP1-Pad3)") (class "Default")
      (node (ref "JP1") (pin "3") (pinfunction "3_3") (pintype "passive"))
    )
    (net (code "77") (name "unconnected-(JP1-Pad4)") (class "Default")
      (node (ref "JP1") (pin "4") (pinfunction "4_4") (pintype "passive"))
    )
    (net (code "78") (name "unconnected-(JP1-Pad5)") (class "Default")
      (node (ref "JP1") (pin "5") (pinfunction "5_5") (pintype "passive"))
    )
    (net (code "79") (name "unconnected-(JP1-Pad6)") (class "Default")
      (node (ref "JP1") (pin "6") (pinfunction "6_6") (pintype "passive"))
    )
    (net (code "80") (name "unconnected-(JP1-Pad7)") (class "Default")
      (node (ref "JP1") (pin "7") (pinfunction "7_7") (pintype "passive"))
    )
    (net (code "81") (name "unconnected-(JP1-Pad8)") (class "Default")
      (node (ref "JP1") (pin "8") (pinfunction "8_8") (pintype "passive"))
    )
    (net (code "82") (name "unconnected-(JP1-Pad9)") (class "Default")
      (node (ref "JP1") (pin "9") (pinfunction "9_9") (pintype "passive"))
    )
    (net (code "83") (name "unconnected-(JP1-Pad10)") (class "Default")
      (node (ref "JP1") (pin "10") (pinfunction "10_10") (pintype "passive"))
    )
    (net (code "84") (name "unconnected-(JP1-Pad11)") (class "Default")
      (node (ref "JP1") (pin "11") (pinfunction "11_11") (pintype "passive"))
    )
    (net (code "85") (name "unconnected-(JP1-Pad12)") (class "Default")
      (node (ref "JP1") (pin "12") (pinfunction "12_12") (pintype "passive"))
    )
    (net (code "86") (name "unconnected-(JP2-Pad1)") (class "Default")
      (node (ref "JP2") (pin "1") (pinfunction "1_1") (pintype "passive"))
    )
    (net (code "87") (name "unconnected-(JP2-Pad2)") (class "Default")
      (node (ref "JP2") (pin "2") (pinfunction "2_2") (pintype "passive"))
    )
    (net (code "88") (name "unconnected-(JP2-Pad3)") (class "Default")
      (node (ref "JP2") (pin "3") (pinfunction "3_3") (pintype "passive"))
    )
    (net (code "89") (name "unconnected-(JP2-Pad4)") (class "Default")
      (node (ref "JP2") (pin "4") (pinfunction "4_4") (pintype "passive"))
    )
    (net (code "90") (name "unconnected-(JP2-Pad5)") (class "Default")
      (node (ref "JP2") (pin "5") (pinfunction "5_5") (pintype "passive"))
    )
    (net (code "91") (name "unconnected-(JP2-Pad6)") (class "Default")
      (node (ref "JP2") (pin "6") (pinfunction "6_6") (pintype "passive"))
    )
    (net (code "92") (name "unconnected-(JP2-Pad7)") (class "Default")
      (node (ref "JP2") (pin "7") (pinfunction "7_7") (pintype "passive"))
    )
    (net (code "93") (name "unconnected-(JP2-Pad8)") (class "Default")
      (node (ref "JP2") (pin "8") (pinfunction "8_8") (pintype "passive"))
    )
    (net (code "94") (name "unconnected-(JP2-Pad9)") (class "Default")
      (node (ref "JP2") (pin "9") (pinfunction "9_9") (pintype "passive"))
    )
    (net (code "95") (name "unconnected-(JP2-Pad10)") (class "Default")
      (node (ref "JP2") (pin "10") (pinfunction "10_10") (pintype "passive"))
    )
    (net (code "96") (name "unconnected-(JP2-Pad11)") (class "Default")
      (node (ref "JP2") (pin "11") (pinfunction "11_11") (pintype "passive"))
    )
    (net (code "97") (name "unconnected-(JP2-Pad12)") (class "Default")
      (node (ref "JP2") (pin "12") (pinfunction "12_12") (pintype "passive"))
    )
    (net (code "98") (name "unconnected-(RASPBERRYPI-Pad1)") (class "Default")
      (node (ref "RASPBERRYPI") (pin "1") (pinfunction "1_1") (pintype "passive"))
    )
    (net (code "99") (name "unconnected-(RASPBERRYPI-Pad3)") (class "Default")
      (node (ref "RASPBERRYPI") (pin "3") (pinfunction "3_3") (pintype "passive"))
    )
    (net (code "100") (name "unconnected-(RASPBERRYPI-Pad4)") (class "Default")
      (node (ref "RASPBERRYPI") (pin "4") (pinfunction "4_4") (pintype "passive"))
    )
    (net (code "101") (name "unconnected-(RASPBERRYPI-Pad6)") (class "Default")
      (node (ref "RASPBERRYPI") (pin "6") (pinfunction "6_6") (pintype "passive"))
    )
    (net (code "102") (name "unconnected-(U$1-ADC-Pad10)") (class "Default")
      (node (ref "U$1") (pin "10") (pinfunction "ADC_10") (pintype "bidirectional"))
    )
    (net (code "103") (name "unconnected-(U$1-GPIO4-Pad6)") (class "Default")
      (node (ref "U$1") (pin "6") (pinfunction "GPIO4_6") (pintype "bidirectional"))
    )
    (net (code "104") (name "unconnected-(U$1-GPIO5-Pad5)") (class "Default")
      (node (ref "U$1") (pin "5") (pinfunction "GPIO5_5") (pintype "bidirectional"))
    )
    (net (code "105") (name "unconnected-(U$1-GPIO12-Pad14)") (class "Default")
      (node (ref "U$1") (pin "14") (pinfunction "GPIO12_14") (pintype "bidirectional"))
    )
    (net (code "106") (name "unconnected-(U$1-GPIO13-Pad15)") (class "Default")
      (node (ref "U$1") (pin "15") (pinfunction "GPIO13_15") (pintype "bidirectional"))
    )
    (net (code "107") (name "unconnected-(U$1-GPIO14-Pad13)") (class "Default")
      (node (ref "U$1") (pin "13") (pinfunction "GPIO14_13") (pintype "bidirectional"))
    )
    (net (code "108") (name "unconnected-(U$1-GPIO16-Pad12)") (class "Default")
      (node (ref "U$1") (pin "12") (pinfunction "GPIO16_12") (pintype "bidirectional"))
    )
    (net (code "109") (name "unconnected-(U$14-PadFFS)") (class "Default")
      (node (ref "U$14") (pin "FFS") (pinfunction "FFS_FFS") (pintype "bidirectional"))
    )
    (net (code "110") (name "unconnected-(U1-PA3-Pad17)") (class "Default")
      (node (ref "U1") (pin "17") (pinfunction "PA3_17") (pintype "bidirectional"))
    )
    (net (code "111") (name "unconnected-(U1-PA4-Pad20)") (class "Default")
      (node (ref "U1") (pin "20") (pinfunction "PA4_20") (pintype "bidirectional"))
    )
    (net (code "112") (name "unconnected-(U1-PA5-Pad21)") (class "Default")
      (node (ref "U1") (pin "21") (pinfunction "PA5_21") (pintype "bidirectional"))
    )
    (net (code "113") (name "unconnected-(U1-PA6-Pad22)") (class "Default")
      (node (ref "U1") (pin "22") (pinfunction "PA6_22") (pintype "bidirectional"))
    )
    (net (code "114") (name "unconnected-(U1-PA7-Pad23)") (class "Default")
      (node (ref "U1") (pin "23") (pinfunction "PA7_23") (pintype "bidirectional"))
    )
    (net (code "115") (name "unconnected-(U1-PA8-Pad41)") (class "Default")
      (node (ref "U1") (pin "41") (pinfunction "PA8_41") (pintype "bidirectional"))
    )
    (net (code "116") (name "unconnected-(U1-PA15-Pad50)") (class "Default")
      (node (ref "U1") (pin "50") (pinfunction "PA15_50") (pintype "bidirectional"))
    )
    (net (code "117") (name "unconnected-(U1-PB2-Pad28)") (class "Default")
      (node (ref "U1") (pin "28") (pinfunction "PB2_28") (pintype "bidirectional"))
    )
    (net (code "118") (name "unconnected-(U1-PB3-Pad55)") (class "Default")
      (node (ref "U1") (pin "55") (pinfunction "PB3_55") (pintype "bidirectional"))
    )
    (net (code "119") (name "unconnected-(U1-PB4-Pad56)") (class "Default")
      (node (ref "U1") (pin "56") (pinfunction "PB4_56") (pintype "bidirectional"))
    )
    (net (code "120") (name "unconnected-(U1-PB5-Pad57)") (class "Default")
      (node (ref "U1") (pin "57") (pinfunction "PB5_57") (pintype "bidirectional"))
    )
    (net (code "121") (name "unconnected-(U1-PB6-Pad58)") (class "Default")
      (node (ref "U1") (pin "58") (pinfunction "PB6_58") (pintype "bidirectional"))
    )
    (net (code "122") (name "unconnected-(U1-PB7-Pad59)") (class "Default")
      (node (ref "U1") (pin "59") (pinfunction "PB7_59") (pintype "bidirectional"))
    )
    (net (code "123") (name "unconnected-(U1-PB8-Pad61)") (class "Default")
      (node (ref "U1") (pin "61") (pinfunction "PB8_61") (pintype "bidirectional"))
    )
    (net (code "124") (name "unconnected-(U1-PB9-Pad62)") (class "Default")
      (node (ref "U1") (pin "62") (pinfunction "PB9_62") (pintype "bidirectional"))
    )
    (net (code "125") (name "unconnected-(U1-PB10-Pad29)") (class "Default")
      (node (ref "U1") (pin "29") (pinfunction "PB10_29") (pintype "bidirectional"))
    )
    (net (code "126") (name "unconnected-(U1-PB11-Pad30)") (class "Default")
      (node (ref "U1") (pin "30") (pinfunction "PB11_30") (pintype "bidirectional"))
    )
    (net (code "127") (name "unconnected-(U1-PB13-Pad34)") (class "Default")
      (node (ref "U1") (pin "34") (pinfunction "PB13_34") (pintype "bidirectional"))
    )
    (net (code "128") (name "unconnected-(U1-PB14-Pad35)") (class "Default")
      (node (ref "U1") (pin "35") (pinfunction "PB14_35") (pintype "bidirectional"))
    )
    (net (code "129") (name "unconnected-(U1-PB15-Pad36)") (class "Default")
      (node (ref "U1") (pin "36") (pinfunction "PB15_36") (pintype "bidirectional"))
    )
    (net (code "130") (name "unconnected-(U1-PC3-Pad11)") (class "Default")
      (node (ref "U1") (pin "11") (pinfunction "PC3_11") (pintype "bidirectional"))
    )
    (net (code "131") (name "unconnected-(U1-PC4-Pad24)") (class "Default")
      (node (ref "U1") (pin "24") (pinfunction "PC4_24") (pintype "bidirectional"))
    )
    (net (code "132") (name "unconnected-(U1-PC5-Pad25)") (class "Default")
      (node (ref "U1") (pin "25") (pinfunction "PC5_25") (pintype "bidirectional"))
    )
    (net (code "133") (name "unconnected-(U1-PC6-Pad37)") (class "Default")
      (node (ref "U1") (pin "37") (pinfunction "PC6_37") (pintype "bidirectional"))
    )
    (net (code "134") (name "unconnected-(U1-PC7-Pad38)") (class "Default")
      (node (ref "U1") (pin "38") (pinfunction "PC7_38") (pintype "bidirectional"))
    )
    (net (code "135") (name "unconnected-(U1-PC8-Pad39)") (class "Default")
      (node (ref "U1") (pin "39") (pinfunction "PC8_39") (pintype "bidirectional"))
    )
    (net (code "136") (name "unconnected-(U1-PC9-Pad40)") (class "Default")
      (node (ref "U1") (pin "40") (pinfunction "PC9_40") (pintype "bidirectional"))
    )
    (net (code "137") (name "unconnected-(U1-PC10-Pad51)") (class "Default")
      (node (ref "U1") (pin "51") (pinfunction "PC10_51") (pintype "bidirectional"))
    )
    (net (code "138") (name "unconnected-(U1-PC11-Pad52)") (class "Default")
      (node (ref "U1") (pin "52") (pinfunction "PC11_52") (pintype "bidirectional"))
    )
    (net (code "139") (name "unconnected-(U1-PC12-Pad53)") (class "Default")
      (node (ref "U1") (pin "53") (pinfunction "PC12_53") (pintype "bidirectional"))
    )
    (net (code "140") (name "unconnected-(U1-PC13-Pad2)") (class "Default")
      (node (ref "U1") (pin "2") (pinfunction "PC13_2") (pintype "bidirectional"))
    )
    (net (code "141") (name "unconnected-(U1-PC14-OSC32_IN-Pad3)") (class "Default")
      (node (ref "U1") (pin "3") (pinfunction "PC14-OSC32_IN_3") (pintype "bidirectional"))
    )
    (net (code "142") (name "unconnected-(U1-PC15-OSC_OUT-Pad4)") (class "Default")
      (node (ref "U1") (pin "4") (pinfunction "PC15-OSC_OUT_4") (pintype "bidirectional"))
    )
    (net (code "143") (name "unconnected-(U1-PD2-Pad54)") (class "Default")
      (node (ref "U1") (pin "54") (pinfunction "PD2_54") (pintype "bidirectional"))
    )
  )
)
